# schematic.net
KiCad netlist of a schematic drawn in EAGLE
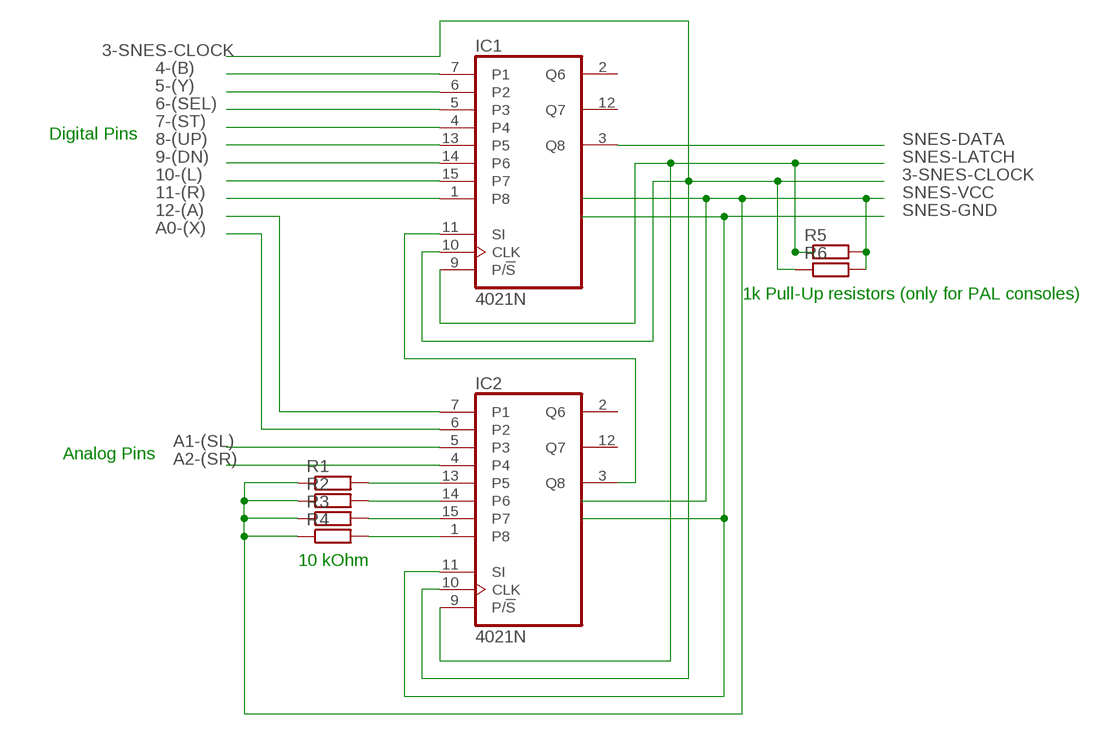
[diagram p0: schematic, sheet 1]

(export (version "E")
  (design (tool "Eeschema 10.0.6"))
  (components
    (comp (ref "IC1")
      (value "4021N")
      (footprint "eagle-import:DIL16")
      (libsource (lib "eagle-import") (part "4021N"))
    )
    (comp (ref "IC2")
      (value "4021N")
      (footprint "eagle-import:DIL16")
      (libsource (lib "eagle-import") (part "4021N"))
    )
    (comp (ref "R1")
      (value "R-EU_0204/2V")
      (footprint "eagle-import:0204V")
      (libsource (lib "eagle-import") (part "R-EU_0204/2V"))
    )
    (comp (ref "R2")
      (value "R-EU_0204/2V")
      (footprint "eagle-import:0204V")
      (libsource (lib "eagle-import") (part "R-EU_0204/2V"))
    )
    (comp (ref "R3")
      (value "R-EU_0204/2V")
      (footprint "eagle-import:0204V")
      (libsource (lib "eagle-import") (part "R-EU_0204/2V"))
    )
    (comp (ref "R4")
      (value "R-EU_0204/2V")
      (footprint "eagle-import:0204V")
      (libsource (lib "eagle-import") (part "R-EU_0204/2V"))
    )
    (comp (ref "R5")
      (value "R-EU_0204/2V")
      (footprint "eagle-import:0204V")
      (libsource (lib "eagle-import") (part "R-EU_0204/2V"))
    )
    (comp (ref "R6")
      (value "R-EU_0204/2V")
      (footprint "eagle-import:0204V")
      (libsource (lib "eagle-import") (part "R-EU_0204/2V"))
    )
  )
  (nets
    (net (code "1") (name "/3-SNES-CLOCK") (class "Default")
      (node (ref "IC1") (pin "10") (pinfunction "CLK_10") (pintype "input"))
      (node (ref "IC2") (pin "10") (pinfunction "CLK_10") (pintype "input"))
      (node (ref "R6") (pin "1") (pinfunction "1_1") (pintype "passive"))
    )
    (net (code "2") (name "/4-(B)") (class "Default")
      (node (ref "IC1") (pin "7") (pinfunction "P1_7") (pintype "input"))
    )
    (net (code "3") (name "/5-(Y)") (class "Default")
      (node (ref "IC1") (pin "6") (pinfunction "P2_6") (pintype "input"))
    )
    (net (code "4") (name "/6-(SEL)") (class "Default")
      (node (ref "IC1") (pin "5") (pinfunction "P3_5") (pintype "input"))
    )
    (net (code "5") (name "/7-(ST)") (class "Default")
      (node (ref "IC1") (pin "4") (pinfunction "P4_4") (pintype "input"))
    )
    (net (code "6") (name "/8-(UP)") (class "Default")
      (node (ref "IC1") (pin "13") (pinfunction "P5_13") (pintype "input"))
    )
    (net (code "7") (name "/9-(DN)") (class "Default")
      (node (ref "IC1") (pin "14") (pinfunction "P6_14") (pintype "input"))
    )
    (net (code "8") (name "/10-(L)") (class "Default")
      (node (ref "IC1") (pin "15") (pinfunction "P7_15") (pintype "input"))
    )
    (net (code "9") (name "/11-(R)") (class "Default")
      (node (ref "IC1") (pin "1") (pinfunction "P8_1") (pintype "input"))
    )
    (net (code "10") (name "/12-(A)") (class "Default")
      (node (ref "IC2") (pin "7") (pinfunction "P1_7") (pintype "input"))
    )
    (net (code "11") (name "/A0-(X)") (class "Default")
      (node (ref "IC2") (pin "6") (pinfunction "P2_6") (pintype "input"))
    )
    (net (code "12") (name "/A1-(SL)") (class "Default")
      (node (ref "IC2") (pin "5") (pinfunction "P3_5") (pintype "input"))
    )
    (net (code "13") (name "/A2-(SR)") (class "Default")
      (node (ref "IC2") (pin "4") (pinfunction "P4_4") (pintype "input"))
    )
    (net (code "14") (name "/SNES-DATA") (class "Default")
      (node (ref "IC1") (pin "3") (pinfunction "Q8_3") (pintype "output"))
    )
    (net (code "15") (name "/SNES-GND") (class "Default")
      (node (ref "IC2") (pin "11") (pinfunction "SI_11") (pintype "input"))
    )
    (net (code "16") (name "/SNES-LATCH") (class "Default")
      (node (ref "IC1") (pin "9") (pinfunction "P/~{S}_9") (pintype "input"))
      (node (ref "IC2") (pin "9") (pinfunction "P/~{S}_9") (pintype "input"))
      (node (ref "R5") (pin "1") (pinfunction "1_1") (pintype "passive"))
    )
    (net (code "17") (name "/SNES-VCC") (class "Default")
      (node (ref "R1") (pin "1") (pinfunction "1_1") (pintype "passive"))
      (node (ref "R2") (pin "1") (pinfunction "1_1") (pintype "passive"))
      (node (ref "R3") (pin "1") (pinfunction "1_1") (pintype "passive"))
      (node (ref "R4") (pin "1") (pinfunction "1_1") (pintype "passive"))
      (node (ref "R5") (pin "2") (pinfunction "2_2") (pintype "passive"))
      (node (ref "R6") (pin "2") (pinfunction "2_2") (pintype "passive"))
    )
    (net (code "18") (name "Net-(IC1A-SI)") (class "Default")
      (node (ref "IC1") (pin "11") (pinfunction "SI_11") (pintype "input"))
      (node (ref "IC2") (pin "3") (pinfunction "Q8_3") (pintype "output"))
    )
    (net (code "19") (name "Net-(IC2A-P5)") (class "Default")
      (node (ref "IC2") (pin "13") (pinfunction "P5_13") (pintype "input"))
      (node (ref "R1") (pin "2") (pinfunction "2_2") (pintype "passive"))
    )
    (net (code "20") (name "Net-(IC2A-P6)") (class "Default")
      (node (ref "IC2") (pin "14") (pinfunction "P6_14") (pintype "input"))
      (node (ref "R2") (pin "2") (pinfunction "2_2") (pintype "passive"))
    )
    (net (code "21") (name "Net-(IC2A-P7)") (class "Default")
      (node (ref "IC2") (pin "15") (pinfunction "P7_15") (pintype "input"))
      (node (ref "R3") (pin "2") (pinfunction "2_2") (pintype "passive"))
    )
    (net (code "22") (name "Net-(IC2A-P8)") (class "Default")
      (node (ref "IC2") (pin "1") (pinfunction "P8_1") (pintype "input"))
      (node (ref "R4") (pin "2") (pinfunction "2_2") (pintype "passive"))
    )
    (net (code "23") (name "unconnected-(IC1A-Q6-Pad2)") (class "Default")
      (node (ref "IC1") (pin "2") (pinfunction "Q6_2") (pintype "output"))
    )
    (net (code "24") (name "unconnected-(IC1A-Q7-Pad12)") (class "Default")
      (node (ref "IC1") (pin "12") (pinfunction "Q7_12") (pintype "output"))
    )
    (net (code "25") (name "unconnected-(IC2A-Q6-Pad2)") (class "Default")
      (node (ref "IC2") (pin "2") (pinfunction "Q6_2") (pintype "output"))
    )
    (net (code "26") (name "unconnected-(IC2A-Q7-Pad12)") (class "Default")
      (node (ref "IC2") (pin "12") (pinfunction "Q7_12") (pintype "output"))
    )
  )
)
